# 4-Connect.net
KiCad netlist of a schematic drawn in Altium Designer
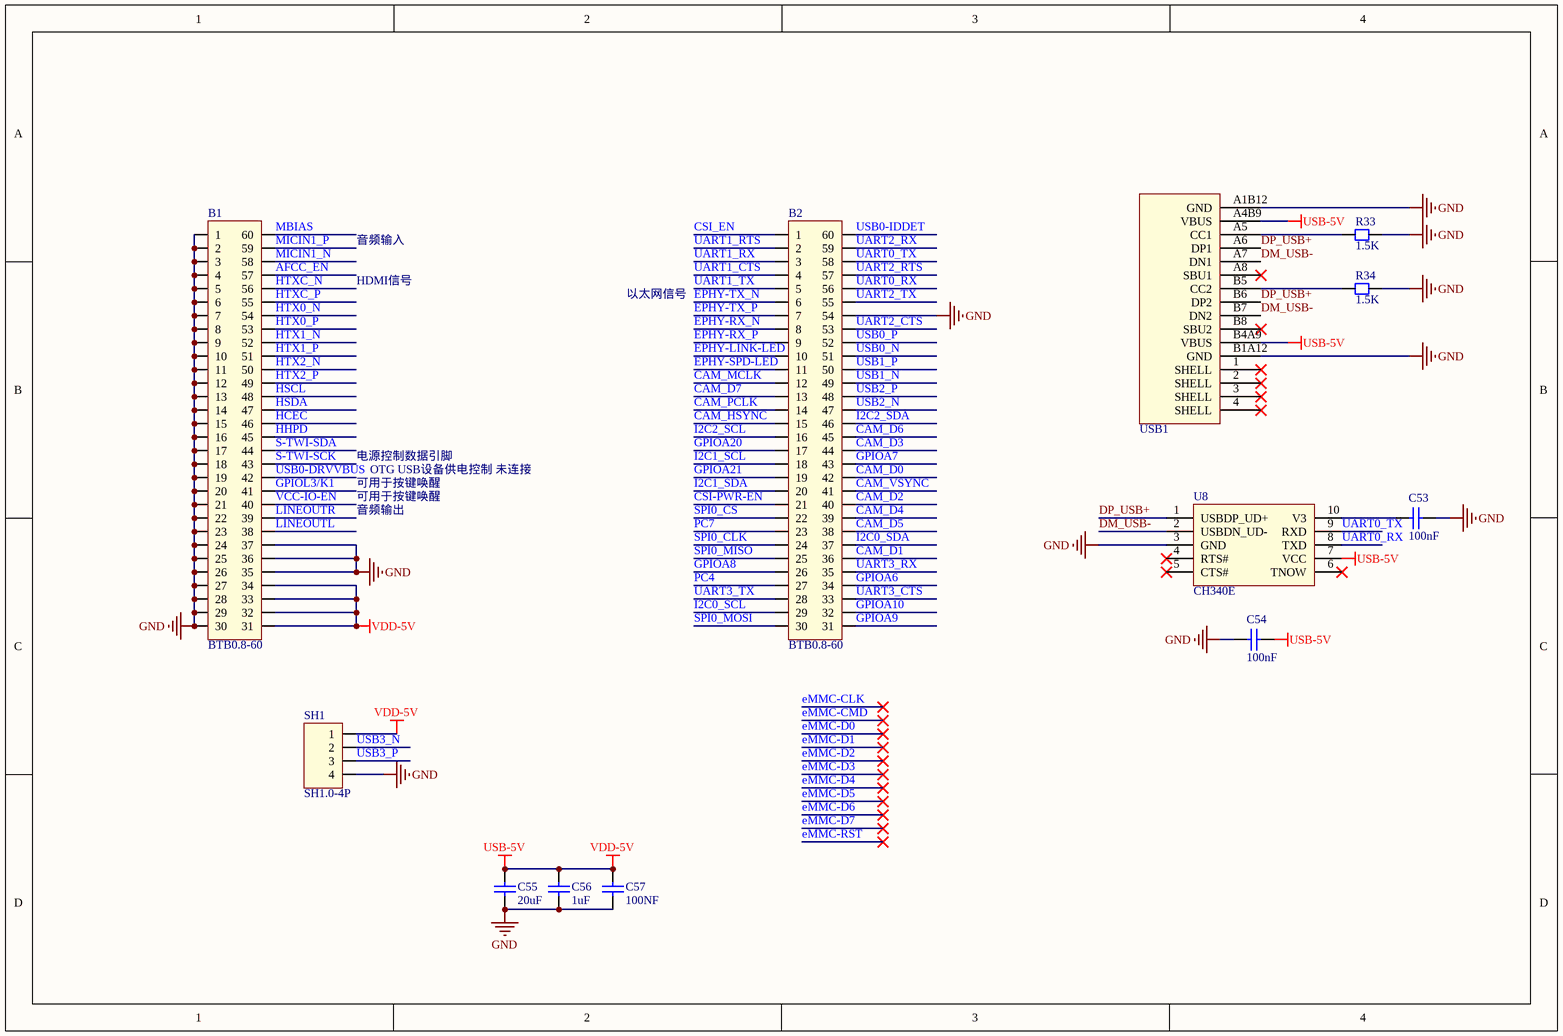
[diagram p0: 4-Connect.SchDoc]

(export (version "E")
  (design (tool "Eeschema 10.0.6"))
  (components
    (comp (ref "B1")
      (value "BTB0.8-60")
      (footprint "BTB0.8-60-SMD")
      (description "板对板连接器 总高度5mm")
      (libsource (lib "tianxiaohua_Schlib") (part "BTB0.8-60"))
    )
    (comp (ref "B2")
      (value "BTB0.8-60")
      (footprint "BTB0.8-60-SMD")
      (description "板对板连接器 总高度5mm")
      (libsource (lib "tianxiaohua_Schlib") (part "BTB0.8-60"))
    )
    (comp (ref "C53")
      (value "100nF")
      (footprint "CC1005-0402")
      (description "贴片电容")
      (libsource (lib "tianxiaohua_Schlib") (part "Chip capacitor"))
    )
    (comp (ref "C54")
      (value "100nF")
      (footprint "CC1005-0402")
      (description "贴片电容")
      (libsource (lib "tianxiaohua_Schlib") (part "Chip capacitor"))
    )
    (comp (ref "C55")
      (value "20uF")
      (footprint "CC2012-0805")
      (description "0805封装的电容")
      (fields (field (name "PUBLISHER") "Altium Limited"))
      (libsource (lib "tianxiaohua_Schlib") (part "Cap Chip 0805"))
    )
    (comp (ref "C56")
      (value "1uF")
      (footprint "CC2012-0805")
      (description "0805封装的电容")
      (fields (field (name "PUBLISHER") "Altium Limited"))
      (libsource (lib "tianxiaohua_Schlib") (part "Cap Chip 0805"))
    )
    (comp (ref "C57")
      (value "100NF")
      (footprint "CC2012-0805")
      (description "0805封装的电容")
      (fields (field (name "PUBLISHER") "Altium Limited"))
      (libsource (lib "tianxiaohua_Schlib") (part "Cap Chip 0805"))
    )
    (comp (ref "R33")
      (value "1.5K")
      (footprint "CR1005-0402")
      (description "贴片电阻")
      (libsource (lib "tianxiaohua_Schlib") (part "Chip resistor"))
    )
    (comp (ref "R34")
      (value "1.5K")
      (footprint "CR1005-0402")
      (description "贴片电阻")
      (libsource (lib "tianxiaohua_Schlib") (part "Chip resistor"))
    )
    (comp (ref "SH1")
      (value "SH1.0-4P")
      (footprint "SH1.0-4P")
      (description "间距为1mm的端子")
      (libsource (lib "tianxiaohua_Schlib") (part "SH1.0-4P"))
    )
    (comp (ref "U8")
      (value "CH340E")
      (footprint "MSOP-10")
      (description "usd转串口芯片 MSOP10封装")
      (libsource (lib "tianxiaohua_Schlib") (part "CH340E"))
    )
    (comp (ref "USB1")
      (value "Tpye-c 16P")
      (footprint "TYPE-C 16P")
      (description "16P 封装的TYPE -c接口 4固定插脚 双向")
      (libsource (lib "tianxiaohua_Schlib") (part "Tpye-c 16P"))
    )
  )
  (nets
    (net (code "1") (name "/AFCC_EN") (class "Default")
      (node (ref "B1") (pin "57") (pinfunction "57_57") (pintype "passive"))
    )
    (net (code "2") (name "/CAM_D0") (class "Default")
      (node (ref "B2") (pin "42") (pinfunction "42_42") (pintype "passive"))
    )
    (net (code "3") (name "/CAM_D1") (class "Default")
      (node (ref "B2") (pin "36") (pinfunction "36_36") (pintype "passive"))
    )
    (net (code "4") (name "/CAM_D2") (class "Default")
      (node (ref "B2") (pin "40") (pinfunction "40_40") (pintype "passive"))
    )
    (net (code "5") (name "/CAM_D3") (class "Default")
      (node (ref "B2") (pin "44") (pinfunction "44_44") (pintype "passive"))
    )
    (net (code "6") (name "/CAM_D4") (class "Default")
      (node (ref "B2") (pin "39") (pinfunction "39_39") (pintype "passive"))
    )
    (net (code "7") (name "/CAM_D5") (class "Default")
      (node (ref "B2") (pin "38") (pinfunction "38_38") (pintype "passive"))
    )
    (net (code "8") (name "/CAM_D6") (class "Default")
      (node (ref "B2") (pin "45") (pinfunction "45_45") (pintype "passive"))
    )
    (net (code "9") (name "/CAM_D7") (class "Default")
      (node (ref "B2") (pin "13") (pinfunction "13_13") (pintype "passive"))
    )
    (net (code "10") (name "/CAM_HSYNC") (class "Default")
      (node (ref "B2") (pin "15") (pinfunction "15_15") (pintype "passive"))
    )
    (net (code "11") (name "/CAM_MCLK") (class "Default")
      (node (ref "B2") (pin "12") (pinfunction "12_12") (pintype "passive"))
    )
    (net (code "12") (name "/CAM_PCLK") (class "Default")
      (node (ref "B2") (pin "14") (pinfunction "14_14") (pintype "passive"))
    )
    (net (code "13") (name "/CAM_VSYNC") (class "Default")
      (node (ref "B2") (pin "41") (pinfunction "41_41") (pintype "passive"))
    )
    (net (code "14") (name "/CSI-PWR-EN") (class "Default")
      (node (ref "B2") (pin "21") (pinfunction "21_21") (pintype "passive"))
    )
    (net (code "15") (name "/CSI_EN") (class "Default")
      (node (ref "B2") (pin "1") (pinfunction "1_1") (pintype "passive"))
    )
    (net (code "16") (name "/DM_USB-") (class "Default")
      (node (ref "U8") (pin "2") (pinfunction "USBDN_UD-_2") (pintype "passive"))
      (node (ref "USB1") (pin "A7") (pinfunction "DN1_A7") (pintype "power_in"))
      (node (ref "USB1") (pin "B7") (pinfunction "DN2_B7") (pintype "power_in"))
    )
    (net (code "17") (name "/DP_USB+") (class "Default")
      (node (ref "U8") (pin "1") (pinfunction "USBDP_UD+_1") (pintype "passive"))
      (node (ref "USB1") (pin "A6") (pinfunction "DP1_A6") (pintype "power_in"))
      (node (ref "USB1") (pin "B6") (pinfunction "DP2_B6") (pintype "power_in"))
    )
    (net (code "18") (name "/EPHY-LINK-LED") (class "Default")
      (node (ref "B2") (pin "10") (pinfunction "10_10") (pintype "passive"))
    )
    (net (code "19") (name "/EPHY-RX_N") (class "Default")
      (node (ref "B2") (pin "8") (pinfunction "8_8") (pintype "passive"))
    )
    (net (code "20") (name "/EPHY-RX_P") (class "Default")
      (node (ref "B2") (pin "9") (pinfunction "9_9") (pintype "passive"))
    )
    (net (code "21") (name "/EPHY-SPD-LED") (class "Default")
      (node (ref "B2") (pin "11") (pinfunction "11_11") (pintype "passive"))
    )
    (net (code "22") (name "/EPHY-TX_N") (class "Default")
      (node (ref "B2") (pin "6") (pinfunction "6_6") (pintype "passive"))
    )
    (net (code "23") (name "/EPHY-TX_P") (class "Default")
      (node (ref "B2") (pin "7") (pinfunction "7_7") (pintype "passive"))
    )
    (net (code "24") (name "/GPIOA6") (class "Default")
      (node (ref "B2") (pin "34") (pinfunction "34_34") (pintype "passive"))
    )
    (net (code "25") (name "/GPIOA7") (class "Default")
      (node (ref "B2") (pin "43") (pinfunction "43_43") (pintype "passive"))
    )
    (net (code "26") (name "/GPIOA8") (class "Default")
      (node (ref "B2") (pin "26") (pinfunction "26_26") (pintype "passive"))
    )
    (net (code "27") (name "/GPIOA9") (class "Default")
      (node (ref "B2") (pin "31") (pinfunction "31_31") (pintype "passive"))
    )
    (net (code "28") (name "/GPIOA10") (class "Default")
      (node (ref "B2") (pin "32") (pinfunction "32_32") (pintype "passive"))
    )
    (net (code "29") (name "/GPIOA20") (class "Default")
      (node (ref "B2") (pin "17") (pinfunction "17_17") (pintype "passive"))
    )
    (net (code "30") (name "/GPIOA21") (class "Default")
      (node (ref "B2") (pin "19") (pinfunction "19_19") (pintype "passive"))
    )
    (net (code "31") (name "/GPIOL3{slash}K1") (class "Default")
      (node (ref "B1") (pin "41") (pinfunction "41_41") (pintype "passive"))
    )
    (net (code "32") (name "/HCEC") (class "Default")
      (node (ref "B1") (pin "46") (pinfunction "46_46") (pintype "passive"))
    )
    (net (code "33") (name "/HHPD") (class "Default")
      (node (ref "B1") (pin "45") (pinfunction "45_45") (pintype "passive"))
    )
    (net (code "34") (name "/HSCL") (class "Default")
      (node (ref "B1") (pin "48") (pinfunction "48_48") (pintype "passive"))
    )
    (net (code "35") (name "/HSDA") (class "Default")
      (node (ref "B1") (pin "47") (pinfunction "47_47") (pintype "passive"))
    )
    (net (code "36") (name "/HTX0_N") (class "Default")
      (node (ref "B1") (pin "54") (pinfunction "54_54") (pintype "passive"))
    )
    (net (code "37") (name "/HTX0_P") (class "Default")
      (node (ref "B1") (pin "53") (pinfunction "53_53") (pintype "passive"))
    )
    (net (code "38") (name "/HTX1_N") (class "Default")
      (node (ref "B1") (pin "52") (pinfunction "52_52") (pintype "passive"))
    )
    (net (code "39") (name "/HTX1_P") (class "Default")
      (node (ref "B1") (pin "51") (pinfunction "51_51") (pintype "passive"))
    )
    (net (code "40") (name "/HTX2_N") (class "Default")
      (node (ref "B1") (pin "50") (pinfunction "50_50") (pintype "passive"))
    )
    (net (code "41") (name "/HTX2_P") (class "Default")
      (node (ref "B1") (pin "49") (pinfunction "49_49") (pintype "passive"))
    )
    (net (code "42") (name "/HTXC_N") (class "Default")
      (node (ref "B1") (pin "56") (pinfunction "56_56") (pintype "passive"))
    )
    (net (code "43") (name "/HTXC_P") (class "Default")
      (node (ref "B1") (pin "55") (pinfunction "55_55") (pintype "passive"))
    )
    (net (code "44") (name "/I2C0_SCL") (class "Default")
      (node (ref "B2") (pin "29") (pinfunction "29_29") (pintype "passive"))
    )
    (net (code "45") (name "/I2C0_SDA") (class "Default")
      (node (ref "B2") (pin "37") (pinfunction "37_37") (pintype "passive"))
    )
    (net (code "46") (name "/I2C1_SCL") (class "Default")
      (node (ref "B2") (pin "18") (pinfunction "18_18") (pintype "passive"))
    )
    (net (code "47") (name "/I2C1_SDA") (class "Default")
      (node (ref "B2") (pin "20") (pinfunction "20_20") (pintype "passive"))
    )
    (net (code "48") (name "/I2C2_SCL") (class "Default")
      (node (ref "B2") (pin "16") (pinfunction "16_16") (pintype "passive"))
    )
    (net (code "49") (name "/I2C2_SDA") (class "Default")
      (node (ref "B2") (pin "46") (pinfunction "46_46") (pintype "passive"))
    )
    (net (code "50") (name "/LINEOUTL") (class "Default")
      (node (ref "B1") (pin "38") (pinfunction "38_38") (pintype "passive"))
    )
    (net (code "51") (name "/LINEOUTR") (class "Default")
      (node (ref "B1") (pin "39") (pinfunction "39_39") (pintype "passive"))
    )
    (net (code "52") (name "/MBIAS") (class "Default")
      (node (ref "B1") (pin "60") (pinfunction "60_60") (pintype "passive"))
    )
    (net (code "53") (name "/MICIN1_N") (class "Default")
      (node (ref "B1") (pin "58") (pinfunction "58_58") (pintype "passive"))
    )
    (net (code "54") (name "/MICIN1_P") (class "Default")
      (node (ref "B1") (pin "59") (pinfunction "59_59") (pintype "passive"))
    )
    (net (code "55") (name "/PC4") (class "Default")
      (node (ref "B2") (pin "27") (pinfunction "27_27") (pintype "passive"))
    )
    (net (code "56") (name "/PC7") (class "Default")
      (node (ref "B2") (pin "23") (pinfunction "23_23") (pintype "passive"))
    )
    (net (code "57") (name "/S-TWI-SCK") (class "Default")
      (node (ref "B1") (pin "43") (pinfunction "43_43") (pintype "passive"))
    )
    (net (code "58") (name "/S-TWI-SDA") (class "Default")
      (node (ref "B1") (pin "44") (pinfunction "44_44") (pintype "passive"))
    )
    (net (code "59") (name "/SPI0_CLK") (class "Default")
      (node (ref "B2") (pin "24") (pinfunction "24_24") (pintype "passive"))
    )
    (net (code "60") (name "/SPI0_CS") (class "Default")
      (node (ref "B2") (pin "22") (pinfunction "22_22") (pintype "passive"))
    )
    (net (code "61") (name "/SPI0_MISO") (class "Default")
      (node (ref "B2") (pin "25") (pinfunction "25_25") (pintype "passive"))
    )
    (net (code "62") (name "/SPI0_MOSI") (class "Default")
      (node (ref "B2") (pin "30") (pinfunction "30_30") (pintype "passive"))
    )
    (net (code "63") (name "/UART0_RX") (class "Default")
      (node (ref "B2") (pin "56") (pinfunction "56_56") (pintype "passive"))
      (node (ref "U8") (pin "8") (pinfunction "TXD_8") (pintype "passive"))
    )
    (net (code "64") (name "/UART0_TX") (class "Default")
      (node (ref "B2") (pin "58") (pinfunction "58_58") (pintype "passive"))
      (node (ref "U8") (pin "9") (pinfunction "RXD_9") (pintype "passive"))
    )
    (net (code "65") (name "/UART1_CTS") (class "Default")
      (node (ref "B2") (pin "4") (pinfunction "4_4") (pintype "passive"))
    )
    (net (code "66") (name "/UART1_RTS") (class "Default")
      (node (ref "B2") (pin "2") (pinfunction "2_2") (pintype "passive"))
    )
    (net (code "67") (name "/UART1_RX") (class "Default")
      (node (ref "B2") (pin "3") (pinfunction "3_3") (pintype "passive"))
    )
    (net (code "68") (name "/UART1_TX") (class "Default")
      (node (ref "B2") (pin "5") (pinfunction "5_5") (pintype "passive"))
    )
    (net (code "69") (name "/UART2_CTS") (class "Default")
      (node (ref "B2") (pin "53") (pinfunction "53_53") (pintype "passive"))
    )
    (net (code "70") (name "/UART2_RTS") (class "Default")
      (node (ref "B2") (pin "57") (pinfunction "57_57") (pintype "passive"))
    )
    (net (code "71") (name "/UART2_RX") (class "Default")
      (node (ref "B2") (pin "59") (pinfunction "59_59") (pintype "passive"))
    )
    (net (code "72") (name "/UART2_TX") (class "Default")
      (node (ref "B2") (pin "55") (pinfunction "55_55") (pintype "passive"))
    )
    (net (code "73") (name "/UART3_CTS") (class "Default")
      (node (ref "B2") (pin "33") (pinfunction "33_33") (pintype "passive"))
    )
    (net (code "74") (name "/UART3_RX") (class "Default")
      (node (ref "B2") (pin "35") (pinfunction "35_35") (pintype "passive"))
    )
    (net (code "75") (name "/UART3_TX") (class "Default")
      (node (ref "B2") (pin "28") (pinfunction "28_28") (pintype "passive"))
    )
    (net (code "76") (name "/USB0-DRVVBUS") (class "Default")
      (node (ref "B1") (pin "42") (pinfunction "42_42") (pintype "passive"))
    )
    (net (code "77") (name "/USB0-IDDET") (class "Default")
      (node (ref "B2") (pin "60") (pinfunction "60_60") (pintype "passive"))
    )
    (net (code "78") (name "/USB0_N") (class "Default")
      (node (ref "B2") (pin "51") (pinfunction "51_51") (pintype "passive"))
    )
    (net (code "79") (name "/USB0_P") (class "Default")
      (node (ref "B2") (pin "52") (pinfunction "52_52") (pintype "passive"))
    )
    (net (code "80") (name "/USB1_N") (class "Default")
      (node (ref "B2") (pin "49") (pinfunction "49_49") (pintype "passive"))
    )
    (net (code "81") (name "/USB1_P") (class "Default")
      (node (ref "B2") (pin "50") (pinfunction "50_50") (pintype "passive"))
    )
    (net (code "82") (name "/USB2_N") (class "Default")
      (node (ref "B2") (pin "47") (pinfunction "47_47") (pintype "passive"))
    )
    (net (code "83") (name "/USB2_P") (class "Default")
      (node (ref "B2") (pin "48") (pinfunction "48_48") (pintype "passive"))
    )
    (net (code "84") (name "/USB3_N") (class "Default")
      (node (ref "SH1") (pin "2") (pinfunction "2_2") (pintype "passive"))
    )
    (net (code "85") (name "/USB3_P") (class "Default")
      (node (ref "SH1") (pin "3") (pinfunction "3_3") (pintype "passive"))
    )
    (net (code "86") (name "/VCC-IO-EN") (class "Default")
      (node (ref "B1") (pin "40") (pinfunction "40_40") (pintype "passive"))
    )
    (net (code "98") (name "GND") (class "Default")
      (node (ref "B1") (pin "1") (pinfunction "1_1") (pintype "passive"))
      (node (ref "B1") (pin "10") (pinfunction "10_10") (pintype "passive"))
      (node (ref "B1") (pin "11") (pinfunction "11_11") (pintype "passive"))
      (node (ref "B1") (pin "12") (pinfunction "12_12") (pintype "passive"))
      (node (ref "B1") (pin "13") (pinfunction "13_13") (pintype "passive"))
      (node (ref "B1") (pin "14") (pinfunction "14_14") (pintype "passive"))
      (node (ref "B1") (pin "15") (pinfunction "15_15") (pintype "passive"))
      (node (ref "B1") (pin "16") (pinfunction "16_16") (pintype "passive"))
      (node (ref "B1") (pin "17") (pinfunction "17_17") (pintype "passive"))
      (node (ref "B1") (pin "18") (pinfunction "18_18") (pintype "passive"))
      (node (ref "B1") (pin "19") (pinfunction "19_19") (pintype "passive"))
      (node (ref "B1") (pin "2") (pinfunction "2_2") (pintype "passive"))
      (node (ref "B1") (pin "20") (pinfunction "20_20") (pintype "passive"))
      (node (ref "B1") (pin "21") (pinfunction "21_21") (pintype "passive"))
      (node (ref "B1") (pin "22") (pinfunction "22_22") (pintype "passive"))
      (node (ref "B1") (pin "23") (pinfunction "23_23") (pintype "passive"))
      (node (ref "B1") (pin "24") (pinfunction "24_24") (pintype "passive"))
      (node (ref "B1") (pin "25") (pinfunction "25_25") (pintype "passive"))
      (node (ref "B1") (pin "26") (pinfunction "26_26") (pintype "passive"))
      (node (ref "B1") (pin "27") (pinfunction "27_27") (pintype "passive"))
      (node (ref "B1") (pin "28") (pinfunction "28_28") (pintype "passive"))
      (node (ref "B1") (pin "29") (pinfunction "29_29") (pintype "passive"))
      (node (ref "B1") (pin "3") (pinfunction "3_3") (pintype "passive"))
      (node (ref "B1") (pin "30") (pinfunction "30_30") (pintype "passive"))
      (node (ref "B1") (pin "35") (pinfunction "35_35") (pintype "passive"))
      (node (ref "B1") (pin "36") (pinfunction "36_36") (pintype "passive"))
      (node (ref "B1") (pin "37") (pinfunction "37_37") (pintype "passive"))
      (node (ref "B1") (pin "4") (pinfunction "4_4") (pintype "passive"))
      (node (ref "B1") (pin "5") (pinfunction "5_5") (pintype "passive"))
      (node (ref "B1") (pin "6") (pinfunction "6_6") (pintype "passive"))
      (node (ref "B1") (pin "7") (pinfunction "7_7") (pintype "passive"))
      (node (ref "B1") (pin "8") (pinfunction "8_8") (pintype "passive"))
      (node (ref "B1") (pin "9") (pinfunction "9_9") (pintype "passive"))
      (node (ref "B2") (pin "54") (pinfunction "54_54") (pintype "passive"))
      (node (ref "C53") (pin "2") (pinfunction "2_2") (pintype "passive"))
      (node (ref "C54") (pin "1") (pinfunction "1_1") (pintype "passive"))
      (node (ref "C55") (pin "1") (pinfunction "1_1") (pintype "passive"))
      (node (ref "C56") (pin "1") (pinfunction "1_1") (pintype "passive"))
      (node (ref "C57") (pin "1") (pinfunction "1_1") (pintype "passive"))
      (node (ref "R33") (pin "1") (pinfunction "1_1") (pintype "passive"))
      (node (ref "R34") (pin "1") (pinfunction "1_1") (pintype "passive"))
      (node (ref "SH1") (pin "4") (pinfunction "4_4") (pintype "passive"))
      (node (ref "U8") (pin "3") (pinfunction "GND_3") (pintype "passive"))
      (node (ref "USB1") (pin "A1B12") (pinfunction "GND_A1B12") (pintype "power_in"))
      (node (ref "USB1") (pin "B1A12") (pinfunction "GND_B1A12") (pintype "power_in"))
    )
    (net (code "99") (name "Net-(U8-V3)") (class "Default")
      (node (ref "C53") (pin "1") (pinfunction "1_1") (pintype "passive"))
      (node (ref "U8") (pin "10") (pinfunction "V3_10") (pintype "passive"))
    )
    (net (code "100") (name "Net-(USB1-CC1)") (class "Default")
      (node (ref "R33") (pin "2") (pinfunction "2_2") (pintype "passive"))
      (node (ref "USB1") (pin "A5") (pinfunction "CC1_A5") (pintype "power_in"))
    )
    (net (code "101") (name "Net-(USB1-CC2)") (class "Default")
      (node (ref "R34") (pin "2") (pinfunction "2_2") (pintype "passive"))
      (node (ref "USB1") (pin "B5") (pinfunction "CC2_B5") (pintype "power_in"))
    )
    (net (code "102") (name "USB-5V") (class "Default")
      (node (ref "B1") (pin "31") (pinfunction "31_31") (pintype "passive"))
      (node (ref "B1") (pin "32") (pinfunction "32_32") (pintype "passive"))
      (node (ref "B1") (pin "33") (pinfunction "33_33") (pintype "passive"))
      (node (ref "B1") (pin "34") (pinfunction "34_34") (pintype "passive"))
      (node (ref "C54") (pin "2") (pinfunction "2_2") (pintype "passive"))
      (node (ref "C55") (pin "2") (pinfunction "2_2") (pintype "passive"))
      (node (ref "C56") (pin "2") (pinfunction "2_2") (pintype "passive"))
      (node (ref "C57") (pin "2") (pinfunction "2_2") (pintype "passive"))
      (node (ref "SH1") (pin "1") (pinfunction "1_1") (pintype "passive"))
      (node (ref "U8") (pin "7") (pinfunction "VCC_7") (pintype "passive"))
      (node (ref "USB1") (pin "A4B9") (pinfunction "VBUS_A4B9") (pintype "power_in"))
      (node (ref "USB1") (pin "B4A9") (pinfunction "VBUS_B4A9") (pintype "power_in"))
    )
    (net (code "103") (name "unconnected-(U8-CTS#-Pad5)") (class "Default")
      (node (ref "U8") (pin "5") (pinfunction "CTS#_5") (pintype "passive+no_connect"))
    )
    (net (code "104") (name "unconnected-(U8-RTS#-Pad4)") (class "Default")
      (node (ref "U8") (pin "4") (pinfunction "RTS#_4") (pintype "passive+no_connect"))
    )
    (net (code "105") (name "unconnected-(U8-TNOW-Pad6)") (class "Default")
      (node (ref "U8") (pin "6") (pinfunction "TNOW_6") (pintype "passive+no_connect"))
    )
    (net (code "106") (name "unconnected-(USB1-SBU1-PadA8)") (class "Default")
      (node (ref "USB1") (pin "A8") (pinfunction "SBU1_A8") (pintype "power_in+no_connect"))
    )
    (net (code "107") (name "unconnected-(USB1-SBU2-PadB8)") (class "Default")
      (node (ref "USB1") (pin "B8") (pinfunction "SBU2_B8") (pintype "power_in+no_connect"))
    )
    (net (code "108") (name "unconnected-(USB1-SHELL-Pad1)") (class "Default")
      (node (ref "USB1") (pin "1") (pinfunction "SHELL_1") (pintype "power_in+no_connect"))
    )
    (net (code "109") (name "unconnected-(USB1-SHELL-Pad2)") (class "Default")
      (node (ref "USB1") (pin "2") (pinfunction "SHELL_2") (pintype "power_in+no_connect"))
    )
    (net (code "110") (name "unconnected-(USB1-SHELL-Pad3)") (class "Default")
      (node (ref "USB1") (pin "3") (pinfunction "SHELL_3") (pintype "power_in+no_connect"))
    )
    (net (code "111") (name "unconnected-(USB1-SHELL-Pad4)") (class "Default")
      (node (ref "USB1") (pin "4") (pinfunction "SHELL_4") (pintype "power_in+no_connect"))
    )
  )
)
